# sensor_board_v0_3.net
KiCad netlist of a schematic drawn in EAGLE
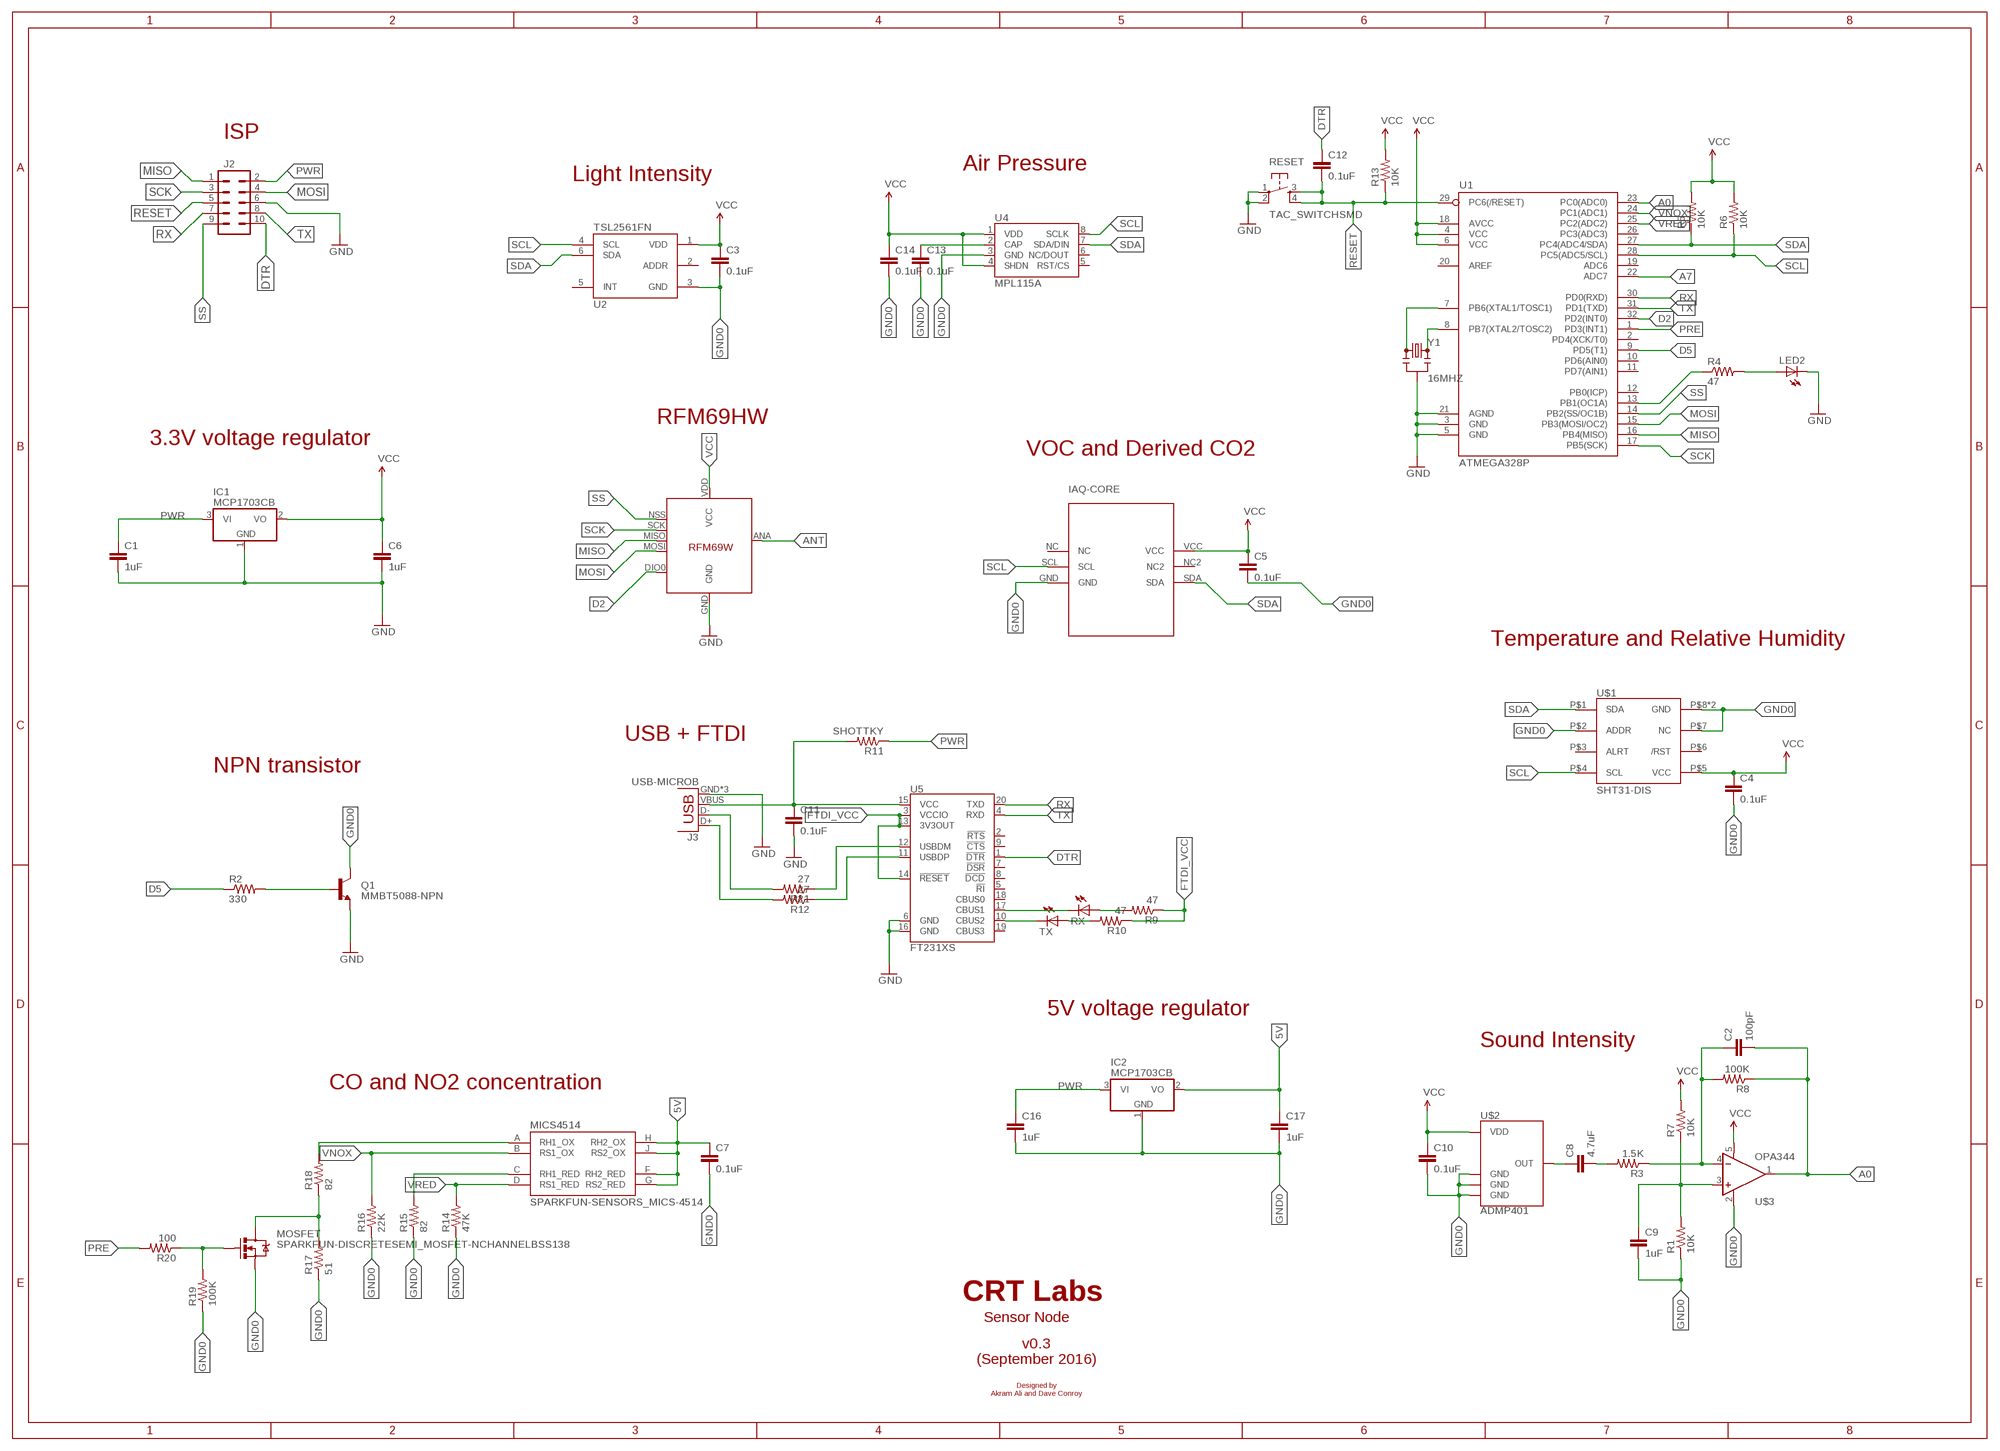
[diagram p0: schematic, sheet 1]

(export (version "E")
  (design (tool "Eeschema 10.0.6"))
  (components
    (comp (ref "C1")
      (value "1uF")
      (footprint "eagle-import:0805")
      (libsource (lib "eagle-import") (part "CAP0805"))
    )
    (comp (ref "C2")
      (value "100pF")
      (footprint "eagle-import:0805")
      (libsource (lib "eagle-import") (part "CAP0805"))
    )
    (comp (ref "C3")
      (value "0.1uF")
      (footprint "eagle-import:0805")
      (libsource (lib "eagle-import") (part "SparkFun-Passives_CAP0805"))
    )
    (comp (ref "C4")
      (value "0.1uF")
      (footprint "eagle-import:0805")
      (libsource (lib "eagle-import") (part "SparkFun-Passives_CAP0805"))
    )
    (comp (ref "C5")
      (value "0.1uF")
      (footprint "eagle-import:0805")
      (libsource (lib "eagle-import") (part "SparkFun-Passives_CAP0805"))
    )
    (comp (ref "C6")
      (value "1uF")
      (footprint "eagle-import:0805")
      (libsource (lib "eagle-import") (part "CAP0805"))
    )
    (comp (ref "C7")
      (value "0.1uF")
      (footprint "eagle-import:0805")
      (libsource (lib "eagle-import") (part "SparkFun-Passives_CAP0805"))
    )
    (comp (ref "C8")
      (value "4.7uF")
      (footprint "eagle-import:0805")
      (libsource (lib "eagle-import") (part "CAP0805"))
    )
    (comp (ref "C9")
      (value "1uF")
      (footprint "eagle-import:0805")
      (libsource (lib "eagle-import") (part "CAP0805"))
    )
    (comp (ref "C10")
      (value "0.1uF")
      (footprint "eagle-import:0805")
      (libsource (lib "eagle-import") (part "CAP0805"))
    )
    (comp (ref "C11")
      (value "0.1uF")
      (footprint "eagle-import:0805")
      (libsource (lib "eagle-import") (part "CAP0805"))
    )
    (comp (ref "C12")
      (value "0.1uF")
      (footprint "eagle-import:0805")
      (libsource (lib "eagle-import") (part "SparkFun-Passives_CAP0805"))
    )
    (comp (ref "C13")
      (value "0.1uF")
      (footprint "eagle-import:0805")
      (libsource (lib "eagle-import") (part "SparkFun-Passives_CAP0805"))
    )
    (comp (ref "C14")
      (value "0.1uF")
      (footprint "eagle-import:0805")
      (libsource (lib "eagle-import") (part "SparkFun-Passives_CAP0805"))
    )
    (comp (ref "C16")
      (value "1uF")
      (footprint "eagle-import:0805")
      (libsource (lib "eagle-import") (part "CAP0805"))
    )
    (comp (ref "C17")
      (value "1uF")
      (footprint "eagle-import:0805")
      (libsource (lib "eagle-import") (part "CAP0805"))
    )
    (comp (ref "IAQ-CORE")
      (value "IAQ-CORE")
      (footprint "eagle-import:IAQ-CORE")
      (fields (field (name "MPN") "IAQ CORE"))
      (libsource (lib "eagle-import") (part "IAQ-CORE"))
    )
    (comp (ref "IC1")
      (value "MCP1703CB")
      (footprint "eagle-import:SOT23")
      (fields (field (name "MPN") "MCP1703T-2502E/CB"))
      (libsource (lib "eagle-import") (part "MCP1703CB"))
    )
    (comp (ref "IC2")
      (value "MCP1703CB")
      (footprint "eagle-import:SOT23")
      (fields (field (name "MPN") "MCP1703T-2502E/CB"))
      (libsource (lib "eagle-import") (part "MCP1703CB"))
    )
    (comp (ref "J2")
      (value "M05X2PTH")
      (footprint "eagle-import:AVR_ICSP")
      (libsource (lib "eagle-import") (part "M05X2PTH"))
    )
    (comp (ref "J3")
      (value "USB-MICROB")
      (footprint "eagle-import:USB-MICROB")
      (libsource (lib "eagle-import") (part "USB-MICROB"))
    )
    (comp (ref "LED2")
      (value "LEDCHIPLED_0805")
      (footprint "eagle-import:CHIPLED_0805")
      (libsource (lib "eagle-import") (part "LEDCHIPLED_0805"))
    )
    (comp (ref "MICS4514")
      (value "SPARKFUN-SENSORS_MICS-4514")
      (footprint "eagle-import:SPARKFUN-SENSORS_MICS_10-SMD")
      (libsource (lib "eagle-import") (part "SPARKFUN-SENSORS_MICS-4514"))
    )
    (comp (ref "MOSFET")
      (value "SPARKFUN-DISCRETESEMI_MOSFET-NCHANNELBSS138")
      (footprint "eagle-import:SPARKFUN-DISCRETESEMI_SOT23-3")
      (libsource (lib "eagle-import") (part "SPARKFUN-DISCRETESEMI_MOSFET-NCHANNELBSS138"))
    )
    (comp (ref "Q1")
      (value "MMBT5088-NPN")
      (footprint "eagle-import:SOT23-3")
      (libsource (lib "eagle-import") (part "TRANSISTOR_NPNMMBT5088"))
    )
    (comp (ref "R1")
      (value "10K")
      (footprint "eagle-import:0805")
      (libsource (lib "eagle-import") (part "RESISTOR0805-RES"))
    )
    (comp (ref "R2")
      (value "330")
      (footprint "eagle-import:0805")
      (libsource (lib "eagle-import") (part "RESISTOR0805-RES"))
    )
    (comp (ref "R3")
      (value "1.5K")
      (footprint "eagle-import:0805")
      (libsource (lib "eagle-import") (part "RESISTOR0805-RES"))
    )
    (comp (ref "R4")
      (value "47")
      (footprint "eagle-import:0805")
      (libsource (lib "eagle-import") (part "SparkFun-Resistors_RESISTOR0805-RES"))
    )
    (comp (ref "R5")
      (value "10K")
      (footprint "eagle-import:0805")
      (libsource (lib "eagle-import") (part "SparkFun-Resistors_RESISTOR0805-RES"))
    )
    (comp (ref "R6")
      (value "10K")
      (footprint "eagle-import:0805")
      (libsource (lib "eagle-import") (part "SparkFun-Resistors_RESISTOR0805-RES"))
    )
    (comp (ref "R7")
      (value "10K")
      (footprint "eagle-import:0805")
      (libsource (lib "eagle-import") (part "RESISTOR0805-RES"))
    )
    (comp (ref "R8")
      (value "100K")
      (footprint "eagle-import:0805")
      (libsource (lib "eagle-import") (part "RESISTOR0805-RES"))
    )
    (comp (ref "R9")
      (value "47")
      (footprint "eagle-import:0805")
      (libsource (lib "eagle-import") (part "RESISTOR0805-RES"))
    )
    (comp (ref "R10")
      (value "47")
      (footprint "eagle-import:0805")
      (libsource (lib "eagle-import") (part "RESISTOR0805-RES"))
    )
    (comp (ref "R11")
      (value "SHOTTKY")
      (footprint "eagle-import:0805")
      (libsource (lib "eagle-import") (part "RESISTOR0805-RES"))
    )
    (comp (ref "R12")
      (value "27")
      (footprint "eagle-import:0805")
      (libsource (lib "eagle-import") (part "RESISTOR0805-RES"))
    )
    (comp (ref "R13")
      (value "10K")
      (footprint "eagle-import:0805")
      (libsource (lib "eagle-import") (part "RESISTOR0805-RES"))
    )
    (comp (ref "R14")
      (value "47K")
      (footprint "eagle-import:0805")
      (libsource (lib "eagle-import") (part "RESISTOR0805-RES"))
    )
    (comp (ref "R15")
      (value "82")
      (footprint "eagle-import:0805")
      (libsource (lib "eagle-import") (part "RESISTOR0805-RES"))
    )
    (comp (ref "R16")
      (value "22K")
      (footprint "eagle-import:0805")
      (libsource (lib "eagle-import") (part "RESISTOR0805-RES"))
    )
    (comp (ref "R17")
      (value "51")
      (footprint "eagle-import:0805")
      (libsource (lib "eagle-import") (part "RESISTOR0805-RES"))
    )
    (comp (ref "R18")
      (value "82")
      (footprint "eagle-import:0805")
      (libsource (lib "eagle-import") (part "RESISTOR0805-RES"))
    )
    (comp (ref "R19")
      (value "100K")
      (footprint "eagle-import:0805")
      (libsource (lib "eagle-import") (part "RESISTOR0805-RES"))
    )
    (comp (ref "R20")
      (value "100")
      (footprint "eagle-import:0805")
      (libsource (lib "eagle-import") (part "RESISTOR0805-RES"))
    )
    (comp (ref "R21")
      (value "27")
      (footprint "eagle-import:0805")
      (libsource (lib "eagle-import") (part "RESISTOR0805-RES"))
    )
    (comp (ref "RESET")
      (value "TAC_SWITCHSMD")
      (footprint "eagle-import:TACTILE-SWITCH-SMD")
      (libsource (lib "eagle-import") (part "TAC_SWITCHSMD"))
    )
    (comp (ref "RX")
      (value "LEDCHIPLED_0805")
      (footprint "eagle-import:CHIPLED_0805")
      (libsource (lib "eagle-import") (part "LEDCHIPLED_0805"))
    )
    (comp (ref "TX")
      (value "LEDCHIPLED_0805")
      (footprint "eagle-import:CHIPLED_0805")
      (libsource (lib "eagle-import") (part "LEDCHIPLED_0805"))
    )
    (comp (ref "U$1")
      (value "SHT31-DIS")
      (footprint "eagle-import:SHT3X")
      (fields (field (name "MPN") "SHT31-DIS-B"))
      (libsource (lib "eagle-import") (part "SHT31-DIS"))
    )
    (comp (ref "U$2")
      (value "ADMP401")
      (footprint "eagle-import:ADMP401")
      (libsource (lib "eagle-import") (part "ADMP401"))
    )
    (comp (ref "U$3")
      (value "OPA344")
      (footprint "eagle-import:SOT23-5")
      (libsource (lib "eagle-import") (part "OPA344"))
    )
    (comp (ref "U$4")
      (value "RFM69HW")
      (footprint "eagle-import:LOWPOWERLAB_RFM69W-MINPADS")
      (libsource (lib "eagle-import") (part "LOWPOWERLAB_RFM69"))
    )
    (comp (ref "U1")
      (value "ATMEGA328P")
      (footprint "eagle-import:TQFP32-08")
      (fields (field (name "MPN") "ATMEGA328PB-AU"))
      (libsource (lib "eagle-import") (part "ATMEGA328P_TQFP"))
    )
    (comp (ref "U2")
      (value "TSL2561FN")
      (footprint "eagle-import:FN-6")
      (fields (field (name "MANF") "AMS-TAOS-USA-Inc."))
      (libsource (lib "eagle-import") (part "TSL2561FN"))
    )
    (comp (ref "U4")
      (value "MPL115A")
      (footprint "eagle-import:LGA8")
      (libsource (lib "eagle-import") (part "MPL115A"))
    )
    (comp (ref "U5")
      (value "FT231XS")
      (footprint "eagle-import:SSOP20_L")
      (libsource (lib "eagle-import") (part "FT231XS"))
    )
    (comp (ref "Y1")
      (value "16MHZ")
      (footprint "eagle-import:RESONATOR-SMD")
      (libsource (lib "eagle-import") (part "RESONATOR16MHZ"))
    )
  )
  (nets
    (net (code "1") (name "5V") (class "Default")
      (node (ref "C17") (pin "1") (pinfunction "1_1") (pintype "passive"))
      (node (ref "C7") (pin "1") (pinfunction "1_1") (pintype "passive"))
      (node (ref "IC2") (pin "2") (pinfunction "VO_2") (pintype "passive"))
      (node (ref "MICS4514") (pin "F") (pinfunction "RH2_RED_F") (pintype "bidirectional"))
      (node (ref "MICS4514") (pin "G") (pinfunction "RS2_RED_G") (pintype "bidirectional"))
      (node (ref "MICS4514") (pin "H") (pinfunction "RH2_OX_H") (pintype "bidirectional"))
      (node (ref "MICS4514") (pin "J") (pinfunction "RS2_OX_J") (pintype "bidirectional"))
    )
    (net (code "2") (name "A0") (class "Default")
      (node (ref "C2") (pin "2") (pinfunction "2_2") (pintype "passive"))
      (node (ref "R8") (pin "1") (pinfunction "1_1") (pintype "passive"))
      (node (ref "U$3") (pin "1") (pinfunction "OUT_1") (pintype "output"))
      (node (ref "U1") (pin "23") (pinfunction "PC0(ADC0)_23") (pintype "bidirectional"))
    )
    (net (code "3") (name "A7") (class "Default")
      (node (ref "U1") (pin "22") (pinfunction "ADC7_22") (pintype "bidirectional"))
    )
    (net (code "4") (name "ANT") (class "Default")
      (node (ref "U$4") (pin "ANA") (pinfunction "ANT_ANA") (pintype "passive"))
    )
    (net (code "5") (name "D2") (class "Default")
      (node (ref "U$4") (pin "DIO0") (pinfunction "DIO0_DIO0") (pintype "open_collector"))
      (node (ref "U1") (pin "32") (pinfunction "PD2(INT0)_32") (pintype "bidirectional"))
    )
    (net (code "6") (name "D5") (class "Default")
      (node (ref "R2") (pin "1") (pinfunction "1_1") (pintype "passive"))
      (node (ref "U1") (pin "9") (pinfunction "PD5(T1)_9") (pintype "bidirectional"))
    )
    (net (code "7") (name "DTR") (class "Default")
      (node (ref "C12") (pin "1") (pinfunction "1_1") (pintype "passive"))
      (node (ref "J2") (pin "10") (pinfunction "10_10") (pintype "passive"))
      (node (ref "U5") (pin "1") (pinfunction "~{DTR}_1") (pintype "bidirectional"))
    )
    (net (code "8") (name "FTDI_VCC") (class "Default")
      (node (ref "R10") (pin "1") (pinfunction "1_1") (pintype "passive"))
      (node (ref "R9") (pin "1") (pinfunction "1_1") (pintype "passive"))
      (node (ref "U5") (pin "13") (pinfunction "3V3OUT_13") (pintype "bidirectional"))
      (node (ref "U5") (pin "14") (pinfunction "~{RESET}_14") (pintype "bidirectional"))
      (node (ref "U5") (pin "3") (pinfunction "VCCIO_3") (pintype "bidirectional"))
    )
    (net (code "9") (name "GND") (class "Default")
      (node (ref "C1") (pin "2") (pinfunction "2_2") (pintype "passive"))
      (node (ref "C11") (pin "2") (pinfunction "2_2") (pintype "passive"))
      (node (ref "C6") (pin "2") (pinfunction "2_2") (pintype "passive"))
      (node (ref "IC1") (pin "1") (pinfunction "GND_1") (pintype "passive"))
      (node (ref "J2") (pin "6") (pinfunction "6_6") (pintype "passive"))
      (node (ref "J3") (pin "GND") (pinfunction "GND_GND") (pintype "bidirectional"))
      (node (ref "J3") (pin "MT1") (pinfunction "GND_MT1") (pintype "bidirectional"))
      (node (ref "J3") (pin "MT2") (pinfunction "GND_MT2") (pintype "bidirectional"))
      (node (ref "LED2") (pin "C") (pinfunction "C_C") (pintype "passive"))
      (node (ref "Q1") (pin "2") (pinfunction "E_2") (pintype "passive"))
      (node (ref "RESET") (pin "1") (pinfunction "1_1") (pintype "passive"))
      (node (ref "RESET") (pin "2") (pinfunction "2_2") (pintype "passive"))
      (node (ref "U$4") (pin "GND") (pinfunction "GND_GND") (pintype "power_in"))
      (node (ref "U1") (pin "21") (pinfunction "AGND_21") (pintype "bidirectional"))
      (node (ref "U1") (pin "3") (pinfunction "GND_3") (pintype "bidirectional"))
      (node (ref "U1") (pin "5") (pinfunction "GND_5") (pintype "bidirectional"))
      (node (ref "U5") (pin "16") (pinfunction "GND_16") (pintype "bidirectional"))
      (node (ref "U5") (pin "6") (pinfunction "GND_6") (pintype "bidirectional"))
      (node (ref "Y1") (pin "2") (pinfunction "2_2") (pintype "passive"))
    )
    (net (code "10") (name "GND0") (class "Default")
      (node (ref "C10") (pin "2") (pinfunction "2_2") (pintype "passive"))
      (node (ref "C13") (pin "2") (pinfunction "2_2") (pintype "passive"))
      (node (ref "C14") (pin "2") (pinfunction "2_2") (pintype "passive"))
      (node (ref "C16") (pin "2") (pinfunction "2_2") (pintype "passive"))
      (node (ref "C17") (pin "2") (pinfunction "2_2") (pintype "passive"))
      (node (ref "C3") (pin "2") (pinfunction "2_2") (pintype "passive"))
      (node (ref "C4") (pin "2") (pinfunction "2_2") (pintype "passive"))
      (node (ref "C5") (pin "2") (pinfunction "2_2") (pintype "passive"))
      (node (ref "C7") (pin "2") (pinfunction "2_2") (pintype "passive"))
      (node (ref "C9") (pin "2") (pinfunction "2_2") (pintype "passive"))
      (node (ref "IAQ-CORE") (pin "GND") (pinfunction "GND_GND") (pintype "bidirectional"))
      (node (ref "IC2") (pin "1") (pinfunction "GND_1") (pintype "passive"))
      (node (ref "MOSFET") (pin "2") (pinfunction "S_2") (pintype "passive"))
      (node (ref "Q1") (pin "3") (pinfunction "C_3") (pintype "passive"))
      (node (ref "R1") (pin "1") (pinfunction "1_1") (pintype "passive"))
      (node (ref "R14") (pin "1") (pinfunction "1_1") (pintype "passive"))
      (node (ref "R15") (pin "1") (pinfunction "1_1") (pintype "passive"))
      (node (ref "R16") (pin "1") (pinfunction "1_1") (pintype "passive"))
      (node (ref "R17") (pin "1") (pinfunction "1_1") (pintype "passive"))
      (node (ref "R19") (pin "1") (pinfunction "1_1") (pintype "passive"))
      (node (ref "U$1") (pin "P$2") (pinfunction "ADDR_P$2") (pintype "bidirectional"))
      (node (ref "U$1") (pin "P$7") (pinfunction "NC_P$7") (pintype "bidirectional"))
      (node (ref "U$1") (pin "P$8") (pinfunction "GND_P$8") (pintype "bidirectional"))
      (node (ref "U$1") (pin "PAD") (pinfunction "GND_PAD") (pintype "bidirectional"))
      (node (ref "U$2") (pin "2") (pinfunction "GND_2") (pintype "bidirectional"))
      (node (ref "U$2") (pin "4") (pinfunction "GND_4") (pintype "bidirectional"))
      (node (ref "U$2") (pin "6") (pinfunction "GND_6") (pintype "bidirectional"))
      (node (ref "U$3") (pin "2") (pinfunction "V-_2") (pintype "power_in"))
      (node (ref "U2") (pin "3") (pinfunction "GND_3") (pintype "power_in"))
      (node (ref "U4") (pin "3") (pinfunction "GND_3") (pintype "bidirectional"))
    )
    (net (code "11") (name "MISO") (class "Default")
      (node (ref "J2") (pin "1") (pinfunction "1_1") (pintype "passive"))
      (node (ref "U$4") (pin "MISO") (pinfunction "MISO_MISO") (pintype "input"))
      (node (ref "U1") (pin "16") (pinfunction "PB4(MISO)_16") (pintype "bidirectional"))
    )
    (net (code "12") (name "MOSI") (class "Default")
      (node (ref "J2") (pin "4") (pinfunction "4_4") (pintype "passive"))
      (node (ref "U$4") (pin "MOSI") (pinfunction "MOSI_MOSI") (pintype "output"))
      (node (ref "U1") (pin "15") (pinfunction "PB3(MOSI/OC2)_15") (pintype "bidirectional"))
    )
    (net (code "13") (name "Net-(C8-Pad2)") (class "Default")
      (node (ref "C8") (pin "2") (pinfunction "2_2") (pintype "passive"))
      (node (ref "R3") (pin "2") (pinfunction "2_2") (pintype "passive"))
    )
    (net (code "14") (name "Net-(J3-PadD+)") (class "Default")
      (node (ref "J3") (pin "D+") (pinfunction "D+_D+") (pintype "bidirectional"))
      (node (ref "R12") (pin "2") (pinfunction "2_2") (pintype "passive"))
    )
    (net (code "15") (name "Net-(J3-PadD-)") (class "Default")
      (node (ref "J3") (pin "D-") (pinfunction "D-_D-") (pintype "bidirectional"))
      (node (ref "R21") (pin "2") (pinfunction "2_2") (pintype "passive"))
    )
    (net (code "16") (name "Net-(LED2-PadA)") (class "Default")
      (node (ref "LED2") (pin "A") (pinfunction "A_A") (pintype "passive"))
      (node (ref "R4") (pin "2") (pinfunction "2_2") (pintype "passive"))
    )
    (net (code "17") (name "Net-(MICS4514-RH1_OX)") (class "Default")
      (node (ref "MICS4514") (pin "A") (pinfunction "RH1_OX_A") (pintype "bidirectional"))
      (node (ref "R18") (pin "2") (pinfunction "2_2") (pintype "passive"))
    )
    (net (code "18") (name "Net-(MICS4514-RH1_RED)") (class "Default")
      (node (ref "MICS4514") (pin "C") (pinfunction "RH1_RED_C") (pintype "bidirectional"))
      (node (ref "R15") (pin "2") (pinfunction "2_2") (pintype "passive"))
    )
    (net (code "19") (name "Net-(MOSFET-D)") (class "Default")
      (node (ref "MOSFET") (pin "3") (pinfunction "D_3") (pintype "passive"))
      (node (ref "R17") (pin "2") (pinfunction "2_2") (pintype "passive"))
      (node (ref "R18") (pin "1") (pinfunction "1_1") (pintype "passive"))
    )
    (net (code "20") (name "Net-(MOSFET-G)") (class "Default")
      (node (ref "MOSFET") (pin "1") (pinfunction "G_1") (pintype "passive"))
      (node (ref "R19") (pin "2") (pinfunction "2_2") (pintype "passive"))
      (node (ref "R20") (pin "1") (pinfunction "1_1") (pintype "passive"))
    )
    (net (code "21") (name "Net-(Q1-B)") (class "Default")
      (node (ref "Q1") (pin "1") (pinfunction "B_1") (pintype "passive"))
      (node (ref "R2") (pin "2") (pinfunction "2_2") (pintype "passive"))
    )
    (net (code "22") (name "Net-(R9-Pad2)") (class "Default")
      (node (ref "R9") (pin "2") (pinfunction "2_2") (pintype "passive"))
      (node (ref "RX") (pin "A") (pinfunction "A_A") (pintype "passive"))
    )
    (net (code "23") (name "Net-(R10-Pad2)") (class "Default")
      (node (ref "R10") (pin "2") (pinfunction "2_2") (pintype "passive"))
      (node (ref "TX") (pin "A") (pinfunction "A_A") (pintype "passive"))
    )
    (net (code "24") (name "Net-(U$2-OUT)") (class "Default")
      (node (ref "C8") (pin "1") (pinfunction "1_1") (pintype "passive"))
      (node (ref "U$2") (pin "1") (pinfunction "OUT_1") (pintype "bidirectional"))
    )
    (net (code "25") (name "Net-(U$3-+IN)") (class "Default")
      (node (ref "C9") (pin "1") (pinfunction "1_1") (pintype "passive"))
      (node (ref "R1") (pin "2") (pinfunction "2_2") (pintype "passive"))
      (node (ref "R7") (pin "1") (pinfunction "1_1") (pintype "passive"))
      (node (ref "U$3") (pin "3") (pinfunction "+IN_3") (pintype "input"))
    )
    (net (code "26") (name "Net-(U$3--IN)") (class "Default")
      (node (ref "C2") (pin "1") (pinfunction "1_1") (pintype "passive"))
      (node (ref "R3") (pin "1") (pinfunction "1_1") (pintype "passive"))
      (node (ref "R8") (pin "2") (pinfunction "2_2") (pintype "passive"))
      (node (ref "U$3") (pin "4") (pinfunction "-IN_4") (pintype "input"))
    )
    (net (code "27") (name "Net-(U1-PB1(OC1A))") (class "Default")
      (node (ref "R4") (pin "1") (pinfunction "1_1") (pintype "passive"))
      (node (ref "U1") (pin "13") (pinfunction "PB1(OC1A)_13") (pintype "bidirectional"))
    )
    (net (code "28") (name "Net-(U1-PB6(XTAL1{slash}TOSC1))") (class "Default")
      (node (ref "U1") (pin "7") (pinfunction "PB6(XTAL1/TOSC1)_7") (pintype "bidirectional"))
      (node (ref "Y1") (pin "1") (pinfunction "1_1") (pintype "passive"))
    )
    (net (code "29") (name "Net-(U1-PB7(XTAL2{slash}TOSC2))") (class "Default")
      (node (ref "U1") (pin "8") (pinfunction "PB7(XTAL2/TOSC2)_8") (pintype "bidirectional"))
      (node (ref "Y1") (pin "3") (pinfunction "3_3") (pintype "passive"))
    )
    (net (code "30") (name "Net-(U4-CAP)") (class "Default")
      (node (ref "C13") (pin "1") (pinfunction "1_1") (pintype "passive"))
      (node (ref "U4") (pin "2") (pinfunction "CAP_2") (pintype "bidirectional"))
    )
    (net (code "31") (name "Net-(U5-CBUS1)") (class "Default")
      (node (ref "RX") (pin "C") (pinfunction "C_C") (pintype "passive"))
      (node (ref "U5") (pin "17") (pinfunction "CBUS1_17") (pintype "bidirectional"))
    )
    (net (code "32") (name "Net-(U5-CBUS2)") (class "Default")
      (node (ref "TX") (pin "C") (pinfunction "C_C") (pintype "passive"))
      (node (ref "U5") (pin "10") (pinfunction "CBUS2_10") (pintype "bidirectional"))
    )
    (net (code "33") (name "Net-(U5-USBDM)") (class "Default")
      (node (ref "R21") (pin "1") (pinfunction "1_1") (pintype "passive"))
      (node (ref "U5") (pin "12") (pinfunction "USBDM_12") (pintype "bidirectional"))
    )
    (net (code "34") (name "Net-(U5-USBDP)") (class "Default")
      (node (ref "R12") (pin "1") (pinfunction "1_1") (pintype "passive"))
      (node (ref "U5") (pin "11") (pinfunction "USBDP_11") (pintype "bidirectional"))
    )
    (net (code "35") (name "Net-(U5-VCC)") (class "Default")
      (node (ref "C11") (pin "1") (pinfunction "1_1") (pintype "passive"))
      (node (ref "J3") (pin "VBUS") (pinfunction "VBUS_VBUS") (pintype "bidirectional"))
      (node (ref "R11") (pin "2") (pinfunction "2_2") (pintype "passive"))
      (node (ref "U5") (pin "15") (pinfunction "VCC_15") (pintype "bidirectional"))
    )
    (net (code "36") (name "PRE") (class "Default")
      (node (ref "R20") (pin "2") (pinfunction "2_2") (pintype "passive"))
      (node (ref "U1") (pin "1") (pinfunction "PD3(INT1)_1") (pintype "bidirectional"))
    )
    (net (code "37") (name "PWR") (class "Default")
      (node (ref "C1") (pin "1") (pinfunction "1_1") (pintype "passive"))
      (node (ref "C16") (pin "1") (pinfunction "1_1") (pintype "passive"))
      (node (ref "IC1") (pin "3") (pinfunction "VI_3") (pintype "input"))
      (node (ref "IC2") (pin "3") (pinfunction "VI_3") (pintype "input"))
      (node (ref "J2") (pin "2") (pinfunction "2_2") (pintype "passive"))
      (node (ref "R11") (pin "1") (pinfunction "1_1") (pintype "passive"))
    )
    (net (code "38") (name "RESET") (class "Default")
      (node (ref "C12") (pin "2") (pinfunction "2_2") (pintype "passive"))
      (node (ref "J2") (pin "5") (pinfunction "5_5") (pintype "passive"))
      (node (ref "R13") (pin "1") (pinfunction "1_1") (pintype "passive"))
      (node (ref "RESET") (pin "3") (pinfunction "3_3") (pintype "passive"))
      (node (ref "RESET") (pin "4") (pinfunction "4_4") (pintype "passive"))
      (node (ref "U1") (pin "29") (pinfunction "PC6(/RESET)_29") (pintype "bidirectional"))
    )
    (net (code "39") (name "RX") (class "Default")
      (node (ref "J2") (pin "7") (pinfunction "7_7") (pintype "passive"))
      (node (ref "U1") (pin "30") (pinfunction "PD0(RXD)_30") (pintype "bidirectional"))
      (node (ref "U5") (pin "20") (pinfunction "TXD_20") (pintype "bidirectional"))
    )
    (net (code "40") (name "SCK") (class "Default")
      (node (ref "J2") (pin "3") (pinfunction "3_3") (pintype "passive"))
      (node (ref "U$4") (pin "SCK") (pinfunction "SCK_SCK") (pintype "input"))
      (node (ref "U1") (pin "17") (pinfunction "PB5(SCK)_17") (pintype "bidirectional"))
    )
    (net (code "41") (name "SCL") (class "Default")
      (node (ref "IAQ-CORE") (pin "SCL") (pinfunction "SCL_SCL") (pintype "bidirectional"))
      (node (ref "R6") (pin "1") (pinfunction "1_1") (pintype "passive"))
      (node (ref "U$1") (pin "P$4") (pinfunction "SCL_P$4") (pintype "bidirectional"))
      (node (ref "U1") (pin "28") (pinfunction "PC5(ADC5/SCL)_28") (pintype "bidirectional"))
      (node (ref "U2") (pin "4") (pinfunction "SCL_4") (pintype "input"))
      (node (ref "U4") (pin "8") (pinfunction "SCLK_8") (pintype "bidirectional"))
    )
    (net (code "42") (name "SDA") (class "Default")
      (node (ref "IAQ-CORE") (pin "SDA") (pinfunction "SDA_SDA") (pintype "bidirectional"))
      (node (ref "R5") (pin "1") (pinfunction "1_1") (pintype "passive"))
      (node (ref "U$1") (pin "P$1") (pinfunction "SDA_P$1") (pintype "bidirectional"))
      (node (ref "U1") (pin "27") (pinfunction "PC4(ADC4/SDA)_27") (pintype "bidirectional"))
      (node (ref "U2") (pin "6") (pinfunction "SDA_6") (pintype "bidirectional"))
      (node (ref "U4") (pin "7") (pinfunction "SDA/DIN_7") (pintype "bidirectional"))
    )
    (net (code "43") (name "SS") (class "Default")
      (node (ref "J2") (pin "9") (pinfunction "9_9") (pintype "passive"))
      (node (ref "U$4") (pin "NSS") (pinfunction "SEL_NSS") (pintype "input"))
      (node (ref "U1") (pin "14") (pinfunction "PB2(SS/OC1B)_14") (pintype "bidirectional"))
    )
    (net (code "44") (name "TX") (class "Default")
      (node (ref "J2") (pin "8") (pinfunction "8_8") (pintype "passive"))
      (node (ref "U1") (pin "31") (pinfunction "PD1(TXD)_31") (pintype "bidirectional"))
      (node (ref "U5") (pin "4") (pinfunction "RXD_4") (pintype "bidirectional"))
    )
    (net (code "45") (name "VCC") (class "Default")
      (node (ref "C10") (pin "1") (pinfunction "1_1") (pintype "passive"))
      (node (ref "C14") (pin "1") (pinfunction "1_1") (pintype "passive"))
      (node (ref "C3") (pin "1") (pinfunction "1_1") (pintype "passive"))
      (node (ref "C4") (pin "1") (pinfunction "1_1") (pintype "passive"))
      (node (ref "C5") (pin "1") (pinfunction "1_1") (pintype "passive"))
      (node (ref "C6") (pin "1") (pinfunction "1_1") (pintype "passive"))
      (node (ref "IAQ-CORE") (pin "VCC") (pinfunction "VCC_VCC") (pintype "bidirectional"))
      (node (ref "IC1") (pin "2") (pinfunction "VO_2") (pintype "passive"))
      (node (ref "R13") (pin "2") (pinfunction "2_2") (pintype "passive"))
      (node (ref "R5") (pin "2") (pinfunction "2_2") (pintype "passive"))
      (node (ref "R6") (pin "2") (pinfunction "2_2") (pintype "passive"))
      (node (ref "R7") (pin "2") (pinfunction "2_2") (pintype "passive"))
      (node (ref "U$1") (pin "P$5") (pinfunction "VCC_P$5") (pintype "bidirectional"))
      (node (ref "U$2") (pin "5") (pinfunction "VDD_5") (pintype "bidirectional"))
      (node (ref "U$3") (pin "5") (pinfunction "V+_5") (pintype "power_in"))
      (node (ref "U$4") (pin "VDD") (pinfunction "VCC_VDD") (pintype "power_in"))
      (node (ref "U1") (pin "18") (pinfunction "AVCC_18") (pintype "bidirectional"))
      (node (ref "U1") (pin "4") (pinfunction "VCC_4") (pintype "bidirectional"))
      (node (ref "U1") (pin "6") (pinfunction "VCC_6") (pintype "bidirectional"))
      (node (ref "U2") (pin "1") (pinfunction "VDD_1") (pintype "power_in"))
      (node (ref "U4") (pin "1") (pinfunction "VDD_1") (pintype "bidirectional"))
      (node (ref "U4") (pin "4") (pinfunction "SHDN_4") (pintype "bidirectional"))
    )
    (net (code "46") (name "VNOX") (class "Default")
      (node (ref "MICS4514") (pin "B") (pinfunction "RS1_OX_B") (pintype "bidirectional"))
      (node (ref "R16") (pin "2") (pinfunction "2_2") (pintype "passive"))
      (node (ref "U1") (pin "24") (pinfunction "PC1(ADC1)_24") (pintype "bidirectional"))
    )
    (net (code "47") (name "VRED") (class "Default")
      (node (ref "MICS4514") (pin "D") (pinfunction "RS1_RED_D") (pintype "bidirectional"))
      (node (ref "R14") (pin "2") (pinfunction "2_2") (pintype "passive"))
      (node (ref "U1") (pin "25") (pinfunction "PC2(ADC2)_25") (pintype "bidirectional"))
    )
    (net (code "48") (name "unconnected-(IAQ-CORE-PadNC)") (class "Default")
      (node (ref "IAQ-CORE") (pin "NC") (pinfunction "NC_NC") (pintype "bidirectional"))
    )
    (net (code "49") (name "unconnected-(IAQ-CORE-PadNC2)") (class "Default")
      (node (ref "IAQ-CORE") (pin "NC2") (pinfunction "NC2_NC2") (pintype "bidirectional"))
    )
    (net (code "50") (name "unconnected-(U$1-ALRT-PadP$3)") (class "Default")
      (node (ref "U$1") (pin "P$3") (pinfunction "ALRT_P$3") (pintype "bidirectional"))
    )
    (net (code "51") (name "unconnected-(U$1-{slash}RST-PadP$6)") (class "Default")
      (node (ref "U$1") (pin "P$6") (pinfunction "/RST_P$6") (pintype "bidirectional"))
    )
    (net (code "52") (name "unconnected-(U1-ADC6-Pad19)") (class "Default")
      (node (ref "U1") (pin "19") (pinfunction "ADC6_19") (pintype "bidirectional"))
    )
    (net (code "53") (name "unconnected-(U1-AREF-Pad20)") (class "Default")
      (node (ref "U1") (pin "20") (pinfunction "AREF_20") (pintype "bidirectional"))
    )
    (net (code "54") (name "unconnected-(U1-PB0(ICP)-Pad12)") (class "Default")
      (node (ref "U1") (pin "12") (pinfunction "PB0(ICP)_12") (pintype "bidirectional"))
    )
    (net (code "55") (name "unconnected-(U1-PC3(ADC3)-Pad26)") (class "Default")
      (node (ref "U1") (pin "26") (pinfunction "PC3(ADC3)_26") (pintype "bidirectional"))
    )
    (net (code "56") (name "unconnected-(U1-PD4(XCK{slash}T0)-Pad2)") (class "Default")
      (node (ref "U1") (pin "2") (pinfunction "PD4(XCK/T0)_2") (pintype "bidirectional"))
    )
    (net (code "57") (name "unconnected-(U1-PD6(AIN0)-Pad10)") (class "Default")
      (node (ref "U1") (pin "10") (pinfunction "PD6(AIN0)_10") (pintype "bidirectional"))
    )
    (net (code "58") (name "unconnected-(U1-PD7(AIN1)-Pad11)") (class "Default")
      (node (ref "U1") (pin "11") (pinfunction "PD7(AIN1)_11") (pintype "bidirectional"))
    )
    (net (code "59") (name "unconnected-(U2-ADDR-Pad2)") (class "Default")
      (node (ref "U2") (pin "2") (pinfunction "ADDR_2") (pintype "input"))
    )
    (net (code "60") (name "unconnected-(U2-INT-Pad5)") (class "Default")
      (node (ref "U2") (pin "5") (pinfunction "INT_5") (pintype "output"))
    )
    (net (code "61") (name "unconnected-(U4-NC{slash}DOUT-Pad6)") (class "Default")
      (node (ref "U4") (pin "6") (pinfunction "NC/DOUT_6") (pintype "bidirectional"))
    )
    (net (code "62") (name "unconnected-(U4-RST{slash}CS-Pad5)") (class "Default")
      (node (ref "U4") (pin "5") (pinfunction "RST/CS_5") (pintype "bidirectional"))
    )
    (net (code "63") (name "unconnected-(U5-CBUS0-Pad18)") (class "Default")
      (node (ref "U5") (pin "18") (pinfunction "CBUS0_18") (pintype "bidirectional"))
    )
    (net (code "64") (name "unconnected-(U5-CBUS3-Pad19)") (class "Default")
      (node (ref "U5") (pin "19") (pinfunction "CBUS3_19") (pintype "bidirectional"))
    )
    (net (code "65") (name "unconnected-(U5-~{CTS}-Pad9)") (class "Default")
      (node (ref "U5") (pin "9") (pinfunction "~{CTS}_9") (pintype "bidirectional"))
    )
    (net (code "66") (name "unconnected-(U5-~{DCD}-Pad8)") (class "Default")
      (node (ref "U5") (pin "8") (pinfunction "~{DCD}_8") (pintype "bidirectional"))
    )
    (net (code "67") (name "unconnected-(U5-~{DSR}-Pad7)") (class "Default")
      (node (ref "U5") (pin "7") (pinfunction "~{DSR}_7") (pintype "bidirectional"))
    )
    (net (code "68") (name "unconnected-(U5-~{RI}-Pad5)") (class "Default")
      (node (ref "U5") (pin "5") (pinfunction "~{RI}_5") (pintype "bidirectional"))
    )
    (net (code "69") (name "unconnected-(U5-~{RTS}-Pad2)") (class "Default")
      (node (ref "U5") (pin "2") (pinfunction "~{RTS}_2") (pintype "bidirectional"))
    )
  )
)
